# USB_Power.net
KiCad netlist of a schematic drawn in Altium Designer
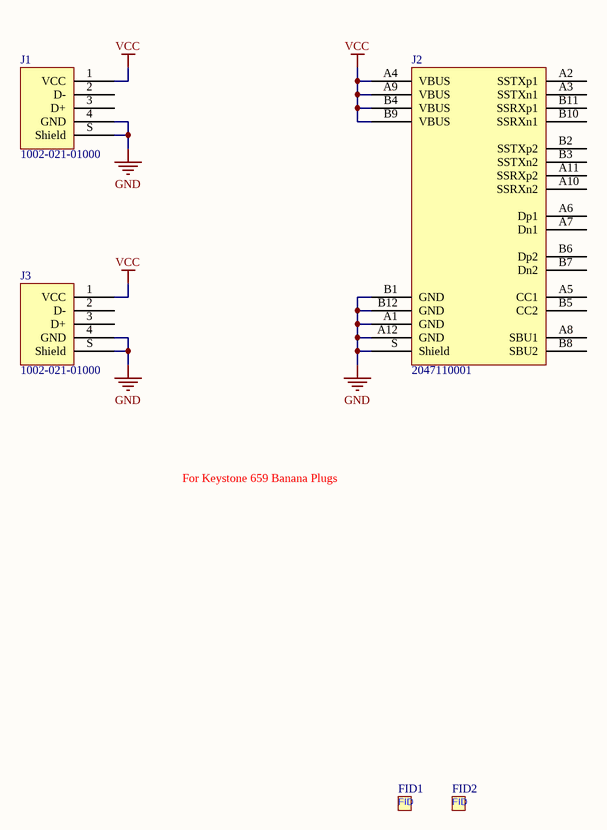
[diagram p0: USB Power.SchDoc]

(export (version "E")
  (design (tool "Eeschema 10.0.6"))
  (components
    (comp (ref "FID1")
      (value "Fiducial")
      (footprint "Fiducial-1mm")
      (libsource (lib "Original Circuit") (part "Fiducial"))
    )
    (comp (ref "FID2")
      (value "Fiducial")
      (footprint "Fiducial-1mm")
      (libsource (lib "Original Circuit") (part "Fiducial"))
    )
    (comp (ref "J1")
      (value "1002-021-01000")
      (footprint "CNC TECH 1002-021-01000")
      (description "CONN RCPT USB2.0 TYPEA 4POS VERT")
      (fields (field (name "MANUFACTURER") "CNC Tech"))
      (libsource (lib "altiumlibrary.com") (part "USB 2.0 TYPE A"))
    )
    (comp (ref "J2")
      (value "2047110001")
      (footprint "Molex 2047110001")
      (description "USB VERTICAL TYPE C 3.1")
      (fields (field (name "MANUFACTURER") "Molex"))
      (libsource (lib "altiumlibrary.com") (part "USB 3.0 Type C"))
    )
    (comp (ref "J3")
      (value "1002-021-01000")
      (footprint "CNC TECH 1002-021-01000")
      (description "CONN RCPT USB2.0 TYPEA 4POS VERT")
      (fields (field (name "MANUFACTURER") "CNC Tech"))
      (libsource (lib "altiumlibrary.com") (part "USB 2.0 TYPE A"))
    )
  )
  (nets
    (net (code "1") (name "GND") (class "Default")
      (node (ref "J1") (pin "4") (pinfunction "GND_4") (pintype "passive"))
      (node (ref "J1") (pin "S") (pinfunction "Shield_S") (pintype "passive"))
      (node (ref "J2") (pin "A1") (pinfunction "GND_A1") (pintype "passive"))
      (node (ref "J2") (pin "A12") (pinfunction "GND_A12") (pintype "passive"))
      (node (ref "J2") (pin "B1") (pinfunction "GND_B1") (pintype "passive"))
      (node (ref "J2") (pin "B12") (pinfunction "GND_B12") (pintype "passive"))
      (node (ref "J2") (pin "S") (pinfunction "Shield_S") (pintype "passive"))
      (node (ref "J3") (pin "4") (pinfunction "GND_4") (pintype "passive"))
      (node (ref "J3") (pin "S") (pinfunction "Shield_S") (pintype "passive"))
    )
    (net (code "2") (name "VCC") (class "Default")
      (node (ref "J1") (pin "1") (pinfunction "VCC_1") (pintype "passive"))
      (node (ref "J2") (pin "A4") (pinfunction "VBUS_A4") (pintype "passive"))
      (node (ref "J2") (pin "A9") (pinfunction "VBUS_A9") (pintype "passive"))
      (node (ref "J2") (pin "B4") (pinfunction "VBUS_B4") (pintype "passive"))
      (node (ref "J2") (pin "B9") (pinfunction "VBUS_B9") (pintype "passive"))
      (node (ref "J3") (pin "1") (pinfunction "VCC_1") (pintype "passive"))
    )
    (net (code "3") (name "unconnected-(J1-D+-Pad3)") (class "Default")
      (node (ref "J1") (pin "3") (pinfunction "D+_3") (pintype "passive"))
    )
    (net (code "4") (name "unconnected-(J1-D--Pad2)") (class "Default")
      (node (ref "J1") (pin "2") (pinfunction "D-_2") (pintype "passive"))
    )
    (net (code "5") (name "unconnected-(J2-CC1-PadA5)") (class "Default")
      (node (ref "J2") (pin "A5") (pinfunction "CC1_A5") (pintype "passive"))
    )
    (net (code "6") (name "unconnected-(J2-CC2-PadB5)") (class "Default")
      (node (ref "J2") (pin "B5") (pinfunction "CC2_B5") (pintype "passive"))
    )
    (net (code "7") (name "unconnected-(J2-Dn1-PadA7)") (class "Default")
      (node (ref "J2") (pin "A7") (pinfunction "Dn1_A7") (pintype "passive"))
    )
    (net (code "8") (name "unconnected-(J2-Dn2-PadB7)") (class "Default")
      (node (ref "J2") (pin "B7") (pinfunction "Dn2_B7") (pintype "passive"))
    )
    (net (code "9") (name "unconnected-(J2-Dp1-PadA6)") (class "Default")
      (node (ref "J2") (pin "A6") (pinfunction "Dp1_A6") (pintype "passive"))
    )
    (net (code "10") (name "unconnected-(J2-Dp2-PadB6)") (class "Default")
      (node (ref "J2") (pin "B6") (pinfunction "Dp2_B6") (pintype "passive"))
    )
    (net (code "11") (name "unconnected-(J2-SBU1-PadA8)") (class "Default")
      (node (ref "J2") (pin "A8") (pinfunction "SBU1_A8") (pintype "passive"))
    )
    (net (code "12") (name "unconnected-(J2-SBU2-PadB8)") (class "Default")
      (node (ref "J2") (pin "B8") (pinfunction "SBU2_B8") (pintype "passive"))
    )
    (net (code "13") (name "unconnected-(J2-SSRXn1-PadB10)") (class "Default")
      (node (ref "J2") (pin "B10") (pinfunction "SSRXn1_B10") (pintype "passive"))
    )
    (net (code "14") (name "unconnected-(J2-SSRXn2-PadA10)") (class "Default")
      (node (ref "J2") (pin "A10") (pinfunction "SSRXn2_A10") (pintype "passive"))
    )
    (net (code "15") (name "unconnected-(J2-SSRXp1-PadB11)") (class "Default")
      (node (ref "J2") (pin "B11") (pinfunction "SSRXp1_B11") (pintype "passive"))
    )
    (net (code "16") (name "unconnected-(J2-SSRXp2-PadA11)") (class "Default")
      (node (ref "J2") (pin "A11") (pinfunction "SSRXp2_A11") (pintype "passive"))
    )
    (net (code "17") (name "unconnected-(J2-SSTXn1-PadA3)") (class "Default")
      (node (ref "J2") (pin "A3") (pinfunction "SSTXn1_A3") (pintype "passive"))
    )
    (net (code "18") (name "unconnected-(J2-SSTXn2-PadB3)") (class "Default")
      (node (ref "J2") (pin "B3") (pinfunction "SSTXn2_B3") (pintype "passive"))
    )
    (net (code "19") (name "unconnected-(J2-SSTXp1-PadA2)") (class "Default")
      (node (ref "J2") (pin "A2") (pinfunction "SSTXp1_A2") (pintype "passive"))
    )
    (net (code "20") (name "unconnected-(J2-SSTXp2-PadB2)") (class "Default")
      (node (ref "J2") (pin "B2") (pinfunction "SSTXp2_B2") (pintype "passive"))
    )
    (net (code "21") (name "unconnected-(J3-D+-Pad3)") (class "Default")
      (node (ref "J3") (pin "3") (pinfunction "D+_3") (pintype "passive"))
    )
    (net (code "22") (name "unconnected-(J3-D--Pad2)") (class "Default")
      (node (ref "J3") (pin "2") (pinfunction "D-_2") (pintype "passive"))
    )
  )
)
